# CoCoEPROMpak.net
KiCad netlist of a schematic drawn in EAGLE
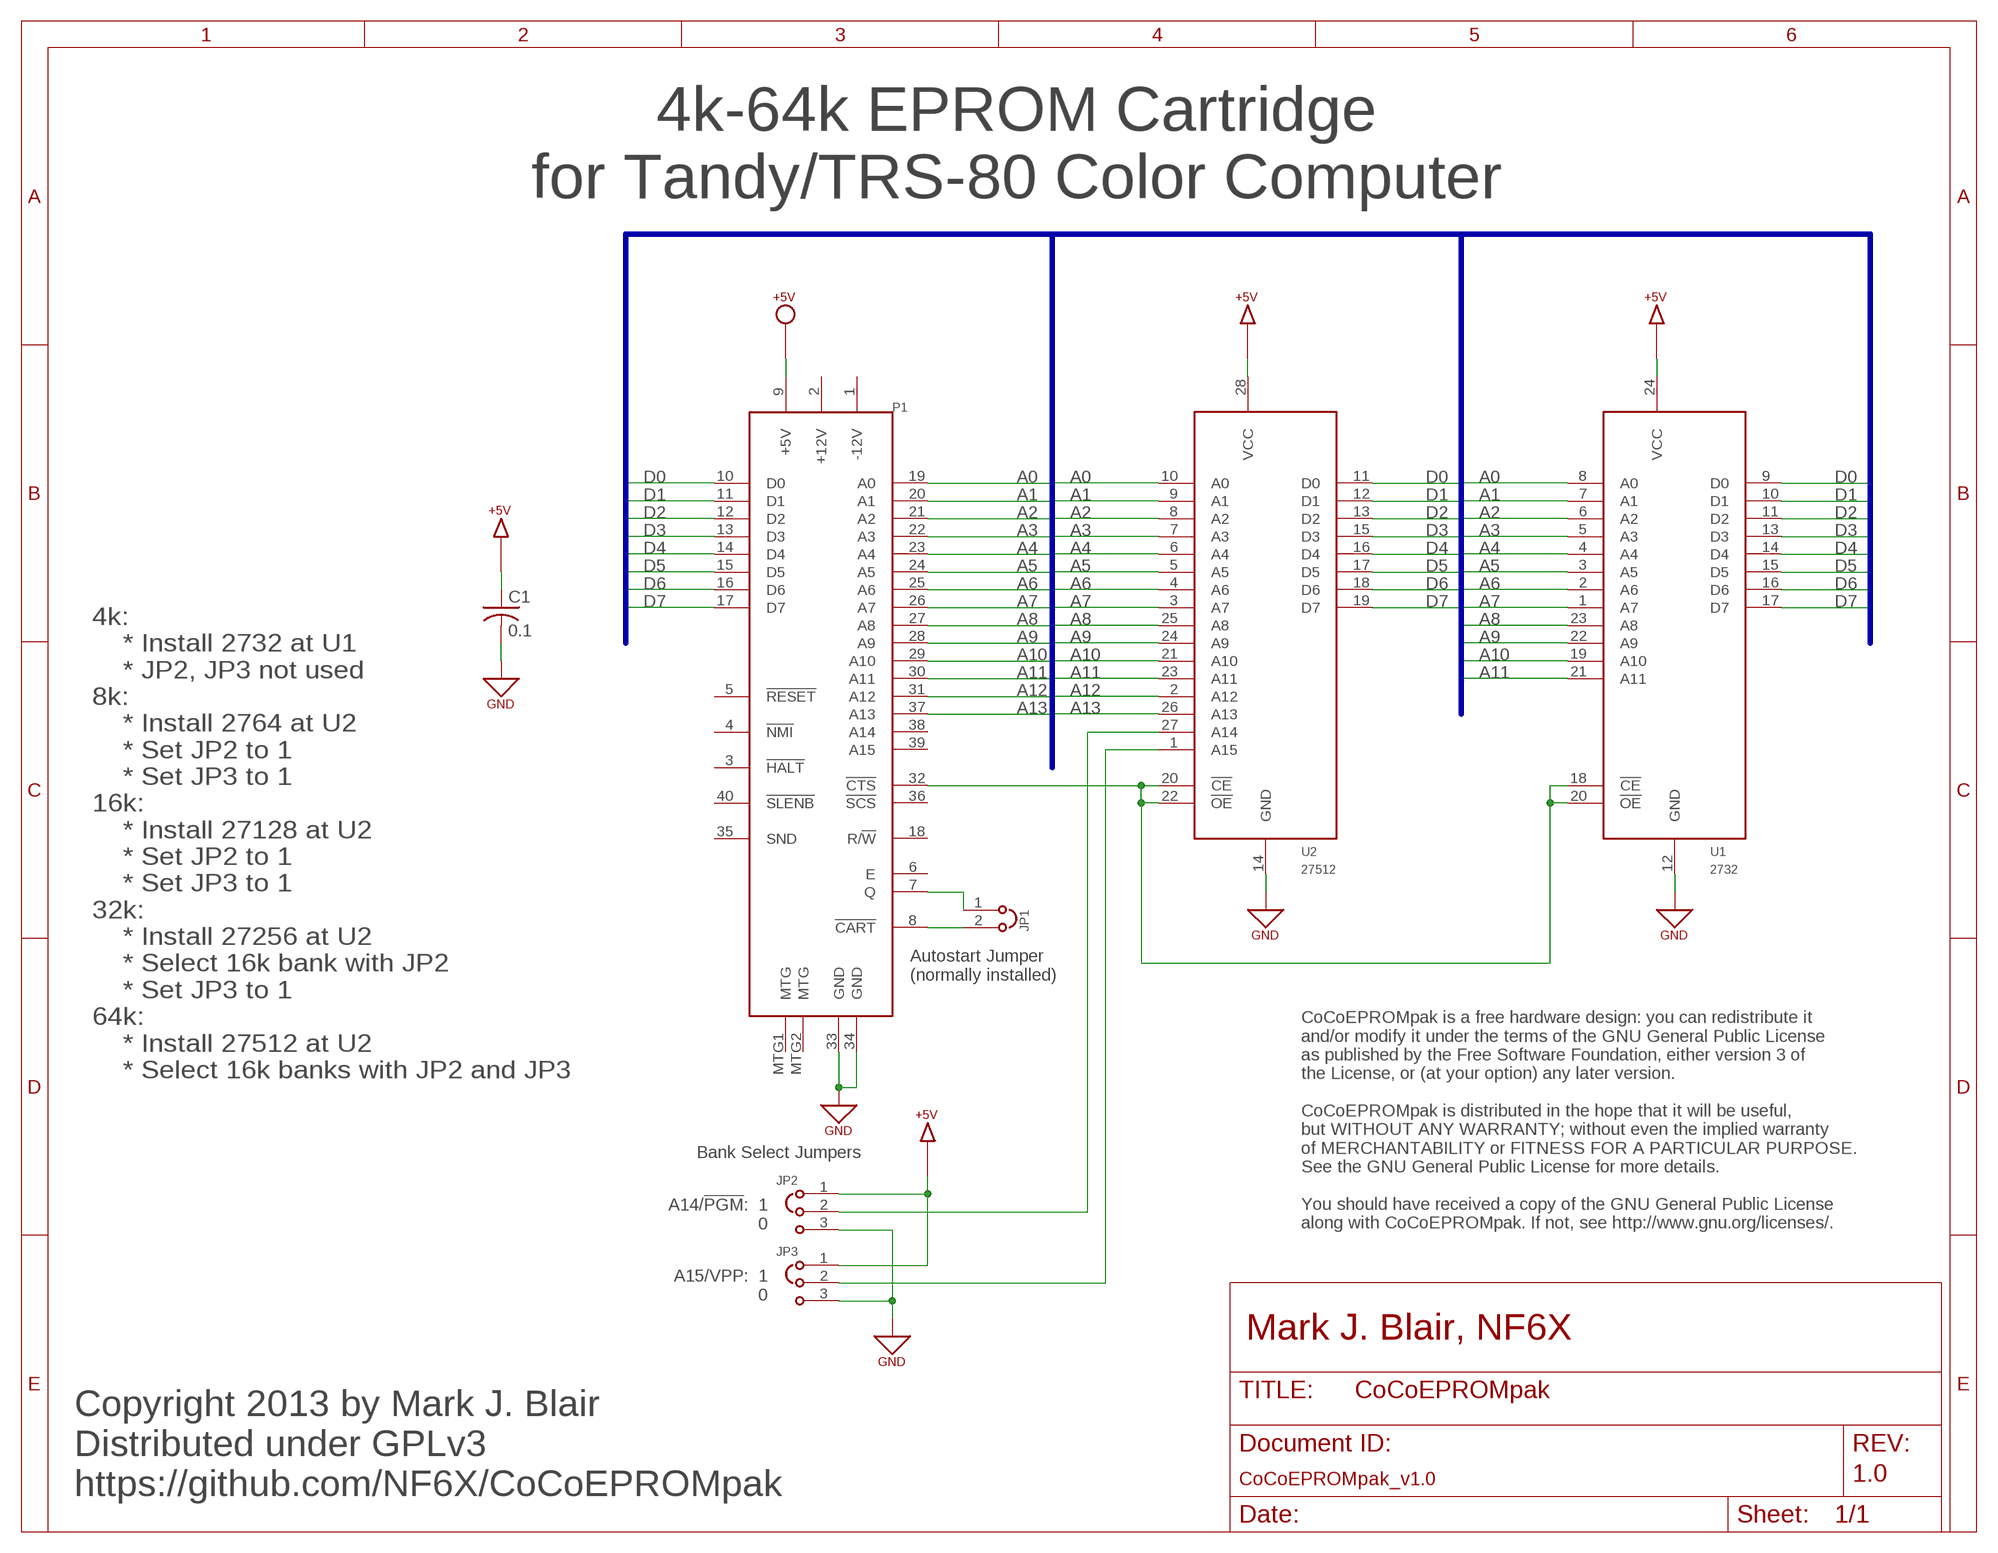
[diagram p0: schematic, sheet 1]

(export (version "E")
  (design (tool "Eeschema 10.0.6"))
  (components
    (comp (ref "C1")
      (value "0.1")
      (footprint "eagle-import:C050-025X075")
      (libsource (lib "eagle-import") (part "C-US050-025X075"))
    )
    (comp (ref "JP1")
      (value "JP2")
      (footprint "eagle-import:JP2-100MIL")
      (libsource (lib "eagle-import") (part "JP2"))
    )
    (comp (ref "JP2")
      (value "JP3")
      (footprint "eagle-import:JP3-100MIL")
      (libsource (lib "eagle-import") (part "JP3"))
    )
    (comp (ref "JP3")
      (value "JP3")
      (footprint "eagle-import:JP3-100MIL")
      (libsource (lib "eagle-import") (part "JP3"))
    )
    (comp (ref "P1")
      (value "COCO-CART")
      (footprint "eagle-import:COCO-CART-2.1X1.75")
      (libsource (lib "eagle-import") (part "COCO-CART"))
    )
    (comp (ref "U1")
      (value "2732")
      (footprint "eagle-import:DIL24")
      (libsource (lib "eagle-import") (part "2732"))
    )
    (comp (ref "U2")
      (value "27512")
      (footprint "eagle-import:DIL28")
      (libsource (lib "eagle-import") (part "27512"))
    )
  )
  (nets
    (net (code "1") (name "+5V_ARROW") (class "Default")
      (node (ref "C1") (pin "1") (pinfunction "1_1") (pintype "passive"))
      (node (ref "JP2") (pin "1") (pinfunction "1_1") (pintype "passive"))
      (node (ref "JP3") (pin "1") (pinfunction "1_1") (pintype "passive"))
      (node (ref "P1") (pin "9") (pinfunction "+5V_9") (pintype "passive"))
      (node (ref "U1") (pin "24") (pinfunction "VCC_24") (pintype "passive"))
      (node (ref "U2") (pin "28") (pinfunction "VCC_28") (pintype "passive"))
    )
    (net (code "2") (name "/A0") (class "Default")
      (node (ref "P1") (pin "19") (pinfunction "A0_19") (pintype "output"))
      (node (ref "U1") (pin "8") (pinfunction "A0_8") (pintype "input"))
      (node (ref "U2") (pin "10") (pinfunction "A0_10") (pintype "input"))
    )
    (net (code "3") (name "/A1") (class "Default")
      (node (ref "P1") (pin "20") (pinfunction "A1_20") (pintype "output"))
      (node (ref "U1") (pin "7") (pinfunction "A1_7") (pintype "input"))
      (node (ref "U2") (pin "9") (pinfunction "A1_9") (pintype "input"))
    )
    (net (code "4") (name "/A2") (class "Default")
      (node (ref "P1") (pin "21") (pinfunction "A2_21") (pintype "output"))
      (node (ref "U1") (pin "6") (pinfunction "A2_6") (pintype "input"))
      (node (ref "U2") (pin "8") (pinfunction "A2_8") (pintype "input"))
    )
    (net (code "5") (name "/A3") (class "Default")
      (node (ref "P1") (pin "22") (pinfunction "A3_22") (pintype "output"))
      (node (ref "U1") (pin "5") (pinfunction "A3_5") (pintype "input"))
      (node (ref "U2") (pin "7") (pinfunction "A3_7") (pintype "input"))
    )
    (net (code "6") (name "/A4") (class "Default")
      (node (ref "P1") (pin "23") (pinfunction "A4_23") (pintype "output"))
      (node (ref "U1") (pin "4") (pinfunction "A4_4") (pintype "input"))
      (node (ref "U2") (pin "6") (pinfunction "A4_6") (pintype "input"))
    )
    (net (code "7") (name "/A5") (class "Default")
      (node (ref "P1") (pin "24") (pinfunction "A5_24") (pintype "output"))
      (node (ref "U1") (pin "3") (pinfunction "A5_3") (pintype "input"))
      (node (ref "U2") (pin "5") (pinfunction "A5_5") (pintype "input"))
    )
    (net (code "8") (name "/A6") (class "Default")
      (node (ref "P1") (pin "25") (pinfunction "A6_25") (pintype "output"))
      (node (ref "U1") (pin "2") (pinfunction "A6_2") (pintype "input"))
      (node (ref "U2") (pin "4") (pinfunction "A6_4") (pintype "input"))
    )
    (net (code "9") (name "/A7") (class "Default")
      (node (ref "P1") (pin "26") (pinfunction "A7_26") (pintype "output"))
      (node (ref "U1") (pin "1") (pinfunction "A7_1") (pintype "input"))
      (node (ref "U2") (pin "3") (pinfunction "A7_3") (pintype "input"))
    )
    (net (code "10") (name "/A8") (class "Default")
      (node (ref "P1") (pin "27") (pinfunction "A8_27") (pintype "output"))
      (node (ref "U1") (pin "23") (pinfunction "A8_23") (pintype "input"))
      (node (ref "U2") (pin "25") (pinfunction "A8_25") (pintype "input"))
    )
    (net (code "11") (name "/A9") (class "Default")
      (node (ref "P1") (pin "28") (pinfunction "A9_28") (pintype "output"))
      (node (ref "U1") (pin "22") (pinfunction "A9_22") (pintype "input"))
      (node (ref "U2") (pin "24") (pinfunction "A9_24") (pintype "input"))
    )
    (net (code "12") (name "/A10") (class "Default")
      (node (ref "P1") (pin "29") (pinfunction "A10_29") (pintype "output"))
      (node (ref "U1") (pin "19") (pinfunction "A10_19") (pintype "input"))
      (node (ref "U2") (pin "21") (pinfunction "A10_21") (pintype "input"))
    )
    (net (code "13") (name "/A11") (class "Default")
      (node (ref "P1") (pin "30") (pinfunction "A11_30") (pintype "output"))
      (node (ref "U1") (pin "21") (pinfunction "A11_21") (pintype "input"))
      (node (ref "U2") (pin "23") (pinfunction "A11_23") (pintype "input"))
    )
    (net (code "14") (name "/A12") (class "Default")
      (node (ref "P1") (pin "31") (pinfunction "A12_31") (pintype "output"))
      (node (ref "U2") (pin "2") (pinfunction "A12_2") (pintype "input"))
    )
    (net (code "15") (name "/A13") (class "Default")
      (node (ref "P1") (pin "37") (pinfunction "A13_37") (pintype "output"))
      (node (ref "U2") (pin "26") (pinfunction "A13_26") (pintype "input"))
    )
    (net (code "16") (name "/D0") (class "Default")
      (node (ref "P1") (pin "10") (pinfunction "D0_10") (pintype "bidirectional"))
      (node (ref "U1") (pin "9") (pinfunction "D0_9") (pintype "output"))
      (node (ref "U2") (pin "11") (pinfunction "D0_11") (pintype "output"))
    )
    (net (code "17") (name "/D1") (class "Default")
      (node (ref "P1") (pin "11") (pinfunction "D1_11") (pintype "bidirectional"))
      (node (ref "U1") (pin "10") (pinfunction "D1_10") (pintype "output"))
      (node (ref "U2") (pin "12") (pinfunction "D1_12") (pintype "output"))
    )
    (net (code "18") (name "/D2") (class "Default")
      (node (ref "P1") (pin "12") (pinfunction "D2_12") (pintype "bidirectional"))
      (node (ref "U1") (pin "11") (pinfunction "D2_11") (pintype "output"))
      (node (ref "U2") (pin "13") (pinfunction "D2_13") (pintype "output"))
    )
    (net (code "19") (name "/D3") (class "Default")
      (node (ref "P1") (pin "13") (pinfunction "D3_13") (pintype "bidirectional"))
      (node (ref "U1") (pin "13") (pinfunction "D3_13") (pintype "output"))
      (node (ref "U2") (pin "15") (pinfunction "D3_15") (pintype "output"))
    )
    (net (code "20") (name "/D4") (class "Default")
      (node (ref "P1") (pin "14") (pinfunction "D4_14") (pintype "bidirectional"))
      (node (ref "U1") (pin "14") (pinfunction "D4_14") (pintype "output"))
      (node (ref "U2") (pin "16") (pinfunction "D4_16") (pintype "output"))
    )
    (net (code "21") (name "/D5") (class "Default")
      (node (ref "P1") (pin "15") (pinfunction "D5_15") (pintype "bidirectional"))
      (node (ref "U1") (pin "15") (pinfunction "D5_15") (pintype "output"))
      (node (ref "U2") (pin "17") (pinfunction "D5_17") (pintype "output"))
    )
    (net (code "22") (name "/D6") (class "Default")
      (node (ref "P1") (pin "16") (pinfunction "D6_16") (pintype "bidirectional"))
      (node (ref "U1") (pin "16") (pinfunction "D6_16") (pintype "output"))
      (node (ref "U2") (pin "18") (pinfunction "D6_18") (pintype "output"))
    )
    (net (code "23") (name "/D7") (class "Default")
      (node (ref "P1") (pin "17") (pinfunction "D7_17") (pintype "bidirectional"))
      (node (ref "U1") (pin "17") (pinfunction "D7_17") (pintype "output"))
      (node (ref "U2") (pin "19") (pinfunction "D7_19") (pintype "output"))
    )
    (net (code "24") (name "GND") (class "Default")
      (node (ref "C1") (pin "2") (pinfunction "2_2") (pintype "passive"))
      (node (ref "JP2") (pin "3") (pinfunction "3_3") (pintype "passive"))
      (node (ref "JP3") (pin "3") (pinfunction "3_3") (pintype "passive"))
      (node (ref "P1") (pin "33") (pinfunction "GND_33") (pintype "passive"))
      (node (ref "P1") (pin "34") (pinfunction "GND_34") (pintype "passive"))
      (node (ref "U1") (pin "12") (pinfunction "GND_12") (pintype "passive"))
      (node (ref "U2") (pin "14") (pinfunction "GND_14") (pintype "passive"))
    )
    (net (code "25") (name "Net-(P1-Q)") (class "Default")
      (node (ref "JP1") (pin "1") (pinfunction "1_1") (pintype "passive"))
      (node (ref "P1") (pin "7") (pinfunction "Q_7") (pintype "output"))
    )
    (net (code "26") (name "Net-(P1-~{CART})") (class "Default")
      (node (ref "JP1") (pin "2") (pinfunction "2_2") (pintype "passive"))
      (node (ref "P1") (pin "8") (pinfunction "~{CART}_8") (pintype "input"))
    )
    (net (code "27") (name "Net-(P1-~{CTS})") (class "Default")
      (node (ref "P1") (pin "32") (pinfunction "~{CTS}_32") (pintype "output"))
      (node (ref "U1") (pin "18") (pinfunction "~{CE}_18") (pintype "input"))
      (node (ref "U1") (pin "20") (pinfunction "~{OE}_20") (pintype "input"))
      (node (ref "U2") (pin "20") (pinfunction "~{CE}_20") (pintype "input"))
      (node (ref "U2") (pin "22") (pinfunction "~{OE}_22") (pintype "input"))
    )
    (net (code "28") (name "Net-(U2-A14)") (class "Default")
      (node (ref "JP2") (pin "2") (pinfunction "2_2") (pintype "passive"))
      (node (ref "U2") (pin "27") (pinfunction "A14_27") (pintype "input"))
    )
    (net (code "29") (name "Net-(U2-A15)") (class "Default")
      (node (ref "JP3") (pin "2") (pinfunction "2_2") (pintype "passive"))
      (node (ref "U2") (pin "1") (pinfunction "A15_1") (pintype "input"))
    )
    (net (code "30") (name "unconnected-(P1-+12V-Pad2)") (class "Default")
      (node (ref "P1") (pin "2") (pinfunction "+12V_2") (pintype "passive"))
    )
    (net (code "31") (name "unconnected-(P1--12V-Pad1)") (class "Default")
      (node (ref "P1") (pin "1") (pinfunction "-12V_1") (pintype "passive"))
    )
    (net (code "32") (name "unconnected-(P1-A14-Pad38)") (class "Default")
      (node (ref "P1") (pin "38") (pinfunction "A14_38") (pintype "output"))
    )
    (net (code "33") (name "unconnected-(P1-A15-Pad39)") (class "Default")
      (node (ref "P1") (pin "39") (pinfunction "A15_39") (pintype "output"))
    )
    (net (code "34") (name "unconnected-(P1-E-Pad6)") (class "Default")
      (node (ref "P1") (pin "6") (pinfunction "E_6") (pintype "output"))
    )
    (net (code "35") (name "unconnected-(P1-MTG-PadMTG1)") (class "Default")
      (node (ref "P1") (pin "MTG1") (pinfunction "MTG_MTG1") (pintype "passive"))
    )
    (net (code "36") (name "unconnected-(P1-MTG-PadMTG2)") (class "Default")
      (node (ref "P1") (pin "MTG2") (pinfunction "MTG_MTG2") (pintype "passive"))
    )
    (net (code "37") (name "unconnected-(P1-R{slash}~{W}-Pad18)") (class "Default")
      (node (ref "P1") (pin "18") (pinfunction "R/~{W}_18") (pintype "output"))
    )
    (net (code "38") (name "unconnected-(P1-SND-Pad35)") (class "Default")
      (node (ref "P1") (pin "35") (pinfunction "SND_35") (pintype "bidirectional"))
    )
    (net (code "39") (name "unconnected-(P1-~{HALT}-Pad3)") (class "Default")
      (node (ref "P1") (pin "3") (pinfunction "~{HALT}_3") (pintype "bidirectional"))
    )
    (net (code "40") (name "unconnected-(P1-~{NMI}-Pad4)") (class "Default")
      (node (ref "P1") (pin "4") (pinfunction "~{NMI}_4") (pintype "bidirectional"))
    )
    (net (code "41") (name "unconnected-(P1-~{RESET}-Pad5)") (class "Default")
      (node (ref "P1") (pin "5") (pinfunction "~{RESET}_5") (pintype "bidirectional"))
    )
    (net (code "42") (name "unconnected-(P1-~{SCS}-Pad36)") (class "Default")
      (node (ref "P1") (pin "36") (pinfunction "~{SCS}_36") (pintype "output"))
    )
    (net (code "43") (name "unconnected-(P1-~{SLENB}-Pad40)") (class "Default")
      (node (ref "P1") (pin "40") (pinfunction "~{SLENB}_40") (pintype "input"))
    )
  )
)
